# IGresupply2-2.net
KiCad netlist of a schematic drawn in Altium Designer
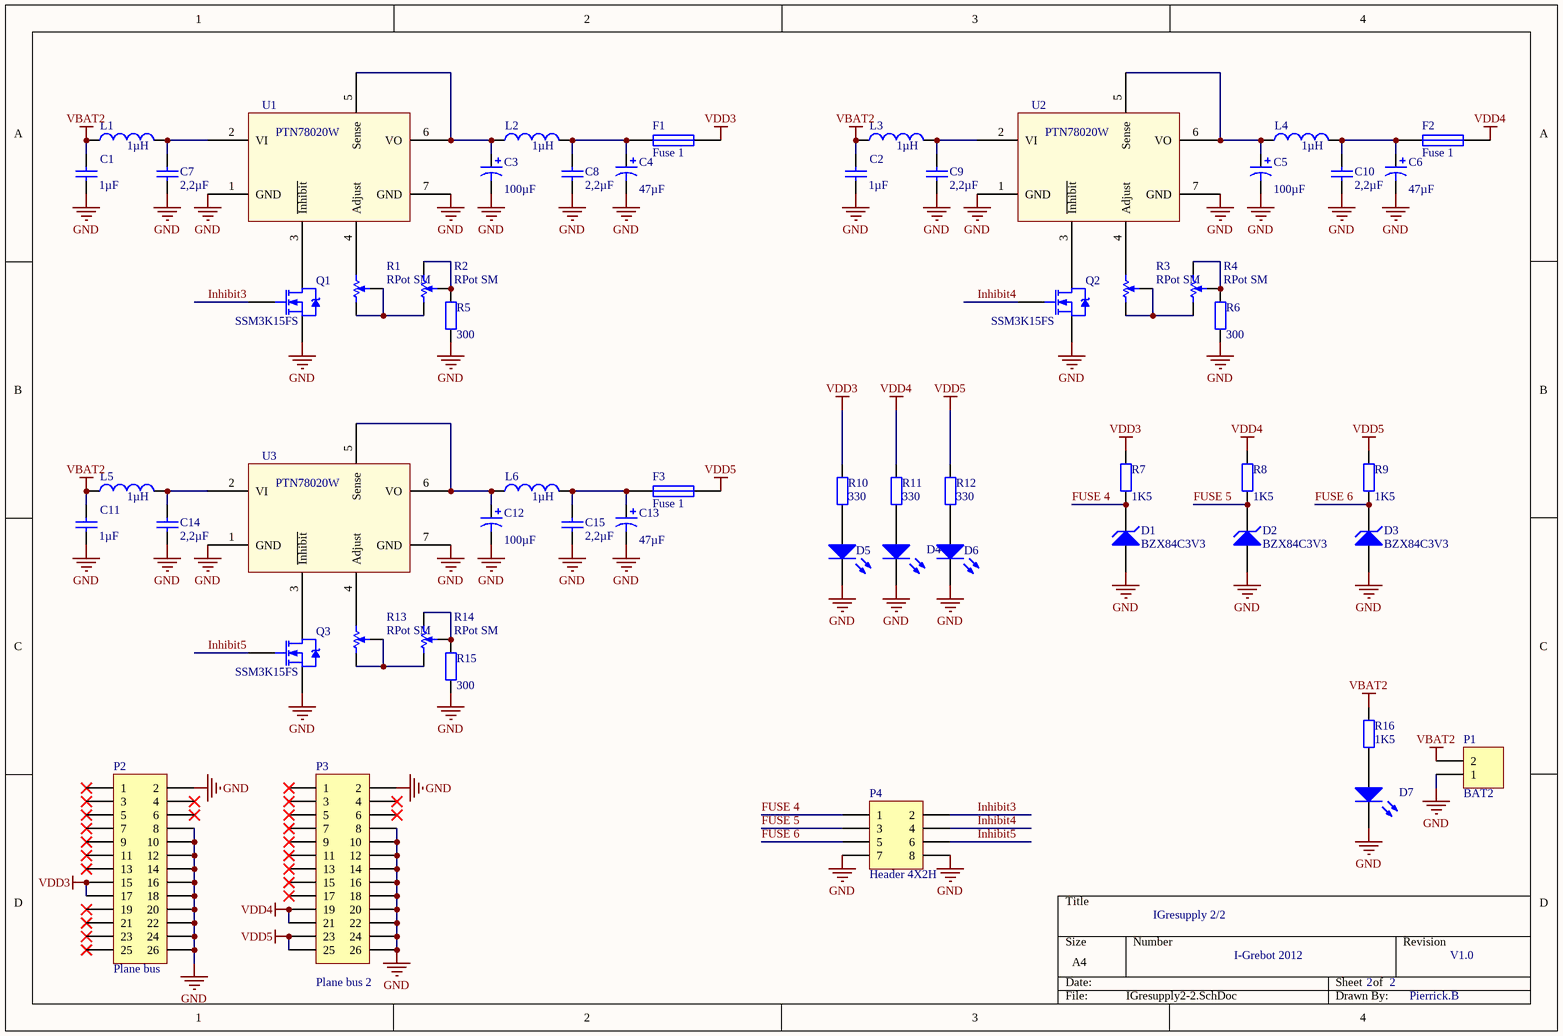
[diagram p0: IGresupply2-2.SchDoc]

(export (version "E")
  (design (tool "Eeschema 10.0.6"))
  (components
    (comp (ref "C1")
      (value "1µF")
      (footprint "Boitier tantale A")
      (description "Capacitor")
      (fields (field (name "Comment") "Cap") (field (name "PUBLISHER") "Altium Limited"))
      (libsource (lib "LIBRARY IGREBOT") (part "Cap"))
    )
    (comp (ref "C2")
      (value "1µF")
      (footprint "Boitier tantale A")
      (description "Capacitor")
      (fields (field (name "Comment") "Cap") (field (name "PUBLISHER") "Altium Limited"))
      (libsource (lib "LIBRARY IGREBOT") (part "Cap"))
    )
    (comp (ref "C3")
      (value "100µF")
      (footprint "Boitier tantale C")
      (description "Polarized Capacitor")
      (fields (field (name "Comment") "Cap Pol") (field (name "PUBLISHER") "Altium Limited"))
      (libsource (lib "LIBRARY IGREBOT") (part "Cap Pol"))
    )
    (comp (ref "C4")
      (value "47µF")
      (footprint "Boitier tantale C")
      (description "Polarized Capacitor")
      (fields (field (name "Comment") "Cap Pol") (field (name "PUBLISHER") "Altium Limited"))
      (libsource (lib "LIBRARY IGREBOT") (part "Cap Pol"))
    )
    (comp (ref "C5")
      (value "100µF")
      (footprint "Boitier tantale C")
      (description "Polarized Capacitor")
      (fields (field (name "Comment") "Cap Pol") (field (name "PUBLISHER") "Altium Limited"))
      (libsource (lib "LIBRARY IGREBOT") (part "Cap Pol"))
    )
    (comp (ref "C6")
      (value "47µF")
      (footprint "Boitier tantale C")
      (description "Polarized Capacitor")
      (fields (field (name "Comment") "Cap Pol") (field (name "PUBLISHER") "Altium Limited"))
      (libsource (lib "LIBRARY IGREBOT") (part "Cap Pol"))
    )
    (comp (ref "C7")
      (value "2,2µF")
      (footprint "Boitier tantale A")
      (description "Capacitor")
      (fields (field (name "Comment") "Cap") (field (name "PUBLISHER") "Altium Limited"))
      (libsource (lib "LIBRARY IGREBOT") (part "Cap"))
    )
    (comp (ref "C8")
      (value "2,2µF")
      (footprint "Boitier tantale A")
      (description "Capacitor")
      (fields (field (name "Comment") "Cap") (field (name "PUBLISHER") "Altium Limited"))
      (libsource (lib "LIBRARY IGREBOT") (part "Cap"))
    )
    (comp (ref "C9")
      (value "2,2µF")
      (footprint "Boitier tantale A")
      (description "Capacitor")
      (fields (field (name "Comment") "Cap") (field (name "PUBLISHER") "Altium Limited"))
      (libsource (lib "LIBRARY IGREBOT") (part "Cap"))
    )
    (comp (ref "C10")
      (value "2,2µF")
      (footprint "Boitier tantale A")
      (description "Capacitor")
      (fields (field (name "Comment") "Cap") (field (name "PUBLISHER") "Altium Limited"))
      (libsource (lib "LIBRARY IGREBOT") (part "Cap"))
    )
    (comp (ref "C11")
      (value "1µF")
      (footprint "Boitier tantale A")
      (description "Capacitor")
      (fields (field (name "Comment") "Cap") (field (name "PUBLISHER") "Altium Limited"))
      (libsource (lib "LIBRARY IGREBOT") (part "Cap"))
    )
    (comp (ref "C12")
      (value "100µF")
      (footprint "Boitier tantale C")
      (description "Polarized Capacitor")
      (fields (field (name "Comment") "Cap Pol") (field (name "PUBLISHER") "Altium Limited"))
      (libsource (lib "LIBRARY IGREBOT") (part "Cap Pol"))
    )
    (comp (ref "C13")
      (value "47µF")
      (footprint "Boitier tantale C")
      (description "Polarized Capacitor")
      (fields (field (name "Comment") "Cap Pol") (field (name "PUBLISHER") "Altium Limited"))
      (libsource (lib "LIBRARY IGREBOT") (part "Cap Pol"))
    )
    (comp (ref "C14")
      (value "2,2µF")
      (footprint "Boitier tantale A")
      (description "Capacitor")
      (fields (field (name "Comment") "Cap") (field (name "PUBLISHER") "Altium Limited"))
      (libsource (lib "LIBRARY IGREBOT") (part "Cap"))
    )
    (comp (ref "C15")
      (value "2,2µF")
      (footprint "Boitier tantale A")
      (description "Capacitor")
      (fields (field (name "Comment") "Cap") (field (name "PUBLISHER") "Altium Limited"))
      (libsource (lib "LIBRARY IGREBOT") (part "Cap"))
    )
    (comp (ref "D1")
      (value "BZX84C3V3")
      (footprint "SOT-23")
      (description "Zener Diode")
      (fields (field (name "PUBLISHER") "Altium Limited"))
      (libsource (lib "LIBRARY IGREBOT") (part "D Zener"))
    )
    (comp (ref "D2")
      (value "BZX84C3V3")
      (footprint "SOT-23")
      (description "Zener Diode")
      (fields (field (name "PUBLISHER") "Altium Limited"))
      (libsource (lib "LIBRARY IGREBOT") (part "D Zener"))
    )
    (comp (ref "D3")
      (value "BZX84C3V3")
      (footprint "SOT-23")
      (description "Zener Diode")
      (fields (field (name "PUBLISHER") "Altium Limited"))
      (libsource (lib "LIBRARY IGREBOT") (part "D Zener"))
    )
    (comp (ref "D4")
      (value "LED1")
      (footprint "HSMS-C110")
      (description "Typical RED GaAs LED")
      (fields (field (name "PUBLISHER") "Altium Limited"))
      (libsource (lib "I-GREBOT 2009") (part "LED1"))
    )
    (comp (ref "D5")
      (value "LED1")
      (footprint "HSMS-C110")
      (description "Typical RED GaAs LED")
      (fields (field (name "PUBLISHER") "Altium Limited"))
      (libsource (lib "I-GREBOT 2009") (part "LED1"))
    )
    (comp (ref "D6")
      (value "LED1")
      (footprint "HSMS-C110")
      (description "Typical RED GaAs LED")
      (fields (field (name "PUBLISHER") "Altium Limited"))
      (libsource (lib "I-GREBOT 2009") (part "LED1"))
    )
    (comp (ref "D7")
      (value "LED1")
      (footprint "HSMS-C110")
      (description "Typical RED GaAs LED")
      (fields (field (name "PUBLISHER") "Altium Limited"))
      (libsource (lib "I-GREBOT 2009") (part "LED1"))
    )
    (comp (ref "F1")
      (value "Fuse 1")
      (footprint "MCCQ-122")
      (description "Fuse")
      (fields (field (name "PUBLISHER") "Altium Limited"))
      (libsource (lib "LIBRARY IGREBOT") (part "Fuse 1"))
    )
    (comp (ref "F2")
      (value "Fuse 1")
      (footprint "MCCQ-122")
      (description "Fuse")
      (fields (field (name "PUBLISHER") "Altium Limited"))
      (libsource (lib "LIBRARY IGREBOT") (part "Fuse 1"))
    )
    (comp (ref "F3")
      (value "Fuse 1")
      (footprint "MCCQ-122")
      (description "Fuse")
      (fields (field (name "PUBLISHER") "Altium Limited"))
      (libsource (lib "LIBRARY IGREBOT") (part "Fuse 1"))
    )
    (comp (ref "L1")
      (value "1µH")
      (footprint "744772010")
      (description "Inductor")
      (fields (field (name "PUBLISHER") "Altium Limited"))
      (libsource (lib "LIBRARY IGREBOT") (part "Inductor"))
    )
    (comp (ref "L2")
      (value "1µH")
      (footprint "744772010")
      (description "Inductor")
      (fields (field (name "PUBLISHER") "Altium Limited"))
      (libsource (lib "LIBRARY IGREBOT") (part "Inductor"))
    )
    (comp (ref "L3")
      (value "1µH")
      (footprint "744772010")
      (description "Inductor")
      (fields (field (name "PUBLISHER") "Altium Limited"))
      (libsource (lib "LIBRARY IGREBOT") (part "Inductor"))
    )
    (comp (ref "L4")
      (value "1µH")
      (footprint "744772010")
      (description "Inductor")
      (fields (field (name "PUBLISHER") "Altium Limited"))
      (libsource (lib "LIBRARY IGREBOT") (part "Inductor"))
    )
    (comp (ref "L5")
      (value "1µH")
      (footprint "744772010")
      (description "Inductor")
      (fields (field (name "PUBLISHER") "Altium Limited"))
      (libsource (lib "LIBRARY IGREBOT") (part "Inductor"))
    )
    (comp (ref "L6")
      (value "1µH")
      (footprint "744772010")
      (description "Inductor")
      (fields (field (name "PUBLISHER") "Altium Limited"))
      (libsource (lib "LIBRARY IGREBOT") (part "Inductor"))
    )
    (comp (ref "P1")
      (value "BAT2")
      (footprint "SL 5.08/90")
      (description "Micro-Fit, 3.0")
      (fields (field (name "PUBLISHER") "Altium Limited"))
      (libsource (lib "I-GREBOT 2010") (part "0436500203"))
    )
    (comp (ref "P2")
      (value "Plane bus")
      (footprint "HDR2X13H")
      (description "Header, 13-Pin, Dual row, Right Angle")
      (fields (field (name "PUBLISHER") "Altium Limited"))
      (libsource (lib "Miscellaneous Connectors") (part "Header 13X2H"))
    )
    (comp (ref "P3")
      (value "Plane bus 2")
      (footprint "HDR2X13H")
      (description "Header, 13-Pin, Dual row, Right Angle")
      (fields (field (name "PUBLISHER") "Altium Limited"))
      (libsource (lib "Miscellaneous Connectors") (part "Header 13X2H"))
    )
    (comp (ref "P4")
      (value "Header 4X2H")
      (footprint "HDR2X4H")
      (description "Header, 4-Pin, Dual row, Right Angle")
      (fields (field (name "PUBLISHER") "Altium Limited"))
      (libsource (lib "Miscellaneous Connectors") (part "Header 4X2H"))
    )
    (comp (ref "Q1")
      (value "SSM3K15FS")
      (footprint "SOT-23")
      (description "N-Channel Power MOSFET")
      (fields (field (name "PUBLISHER") "Altium Limited"))
      (libsource (lib "LIBRARY IGREBOT") (part "NMOS-2"))
    )
    (comp (ref "Q2")
      (value "SSM3K15FS")
      (footprint "SOT-23")
      (description "N-Channel Power MOSFET")
      (fields (field (name "PUBLISHER") "Altium Limited"))
      (libsource (lib "LIBRARY IGREBOT") (part "NMOS-2"))
    )
    (comp (ref "Q3")
      (value "SSM3K15FS")
      (footprint "SOT-23")
      (description "N-Channel Power MOSFET")
      (fields (field (name "PUBLISHER") "Altium Limited"))
      (libsource (lib "LIBRARY IGREBOT") (part "NMOS-2"))
    )
    (comp (ref "R1")
      (value "RPot SM")
      (footprint "3296X")
      (description "Square Trimming Potentiometer")
      (fields (field (name "PUBLISHER") "Altium Limited"))
      (libsource (lib "LIBRARY IGREBOT") (part "RPot SM"))
    )
    (comp (ref "R2")
      (value "RPot SM")
      (footprint "3296X")
      (description "Square Trimming Potentiometer")
      (fields (field (name "PUBLISHER") "Altium Limited"))
      (libsource (lib "LIBRARY IGREBOT") (part "RPot SM"))
    )
    (comp (ref "R3")
      (value "RPot SM")
      (footprint "3296X")
      (description "Square Trimming Potentiometer")
      (fields (field (name "PUBLISHER") "Altium Limited"))
      (libsource (lib "LIBRARY IGREBOT") (part "RPot SM"))
    )
    (comp (ref "R4")
      (value "RPot SM")
      (footprint "3296X")
      (description "Square Trimming Potentiometer")
      (fields (field (name "PUBLISHER") "Altium Limited"))
      (libsource (lib "LIBRARY IGREBOT") (part "RPot SM"))
    )
    (comp (ref "R5")
      (value "300")
      (footprint "0805")
      (description "Resistor")
      (fields (field (name "Comment") "Res2") (field (name "PUBLISHER") "Altium Limited"))
      (libsource (lib "LIBRARY IGREBOT") (part "Res2"))
    )
    (comp (ref "R6")
      (value "300")
      (footprint "0805")
      (description "Resistor")
      (fields (field (name "Comment") "Res2") (field (name "PUBLISHER") "Altium Limited"))
      (libsource (lib "LIBRARY IGREBOT") (part "Res2"))
    )
    (comp (ref "R7")
      (value "1K5")
      (footprint "0805")
      (description "Resistor")
      (fields (field (name "Comment") "Res2") (field (name "PUBLISHER") "Altium Limited"))
      (libsource (lib "LIBRARY IGREBOT") (part "Res2"))
    )
    (comp (ref "R8")
      (value "1K5")
      (footprint "0805")
      (description "Resistor")
      (fields (field (name "Comment") "Res2") (field (name "PUBLISHER") "Altium Limited"))
      (libsource (lib "LIBRARY IGREBOT") (part "Res2"))
    )
    (comp (ref "R9")
      (value "1K5")
      (footprint "0805")
      (description "Resistor")
      (fields (field (name "Comment") "Res2") (field (name "PUBLISHER") "Altium Limited"))
      (libsource (lib "LIBRARY IGREBOT") (part "Res2"))
    )
    (comp (ref "R10")
      (value "330")
      (footprint "0805")
      (description "Resistor")
      (fields (field (name "Comment") "Res2") (field (name "PUBLISHER") "Altium Limited"))
      (libsource (lib "*") (part "Res2"))
    )
    (comp (ref "R11")
      (value "330")
      (footprint "0805")
      (description "Resistor")
      (fields (field (name "Comment") "Res2") (field (name "PUBLISHER") "Altium Limited"))
      (libsource (lib "*") (part "Res2"))
    )
    (comp (ref "R12")
      (value "330")
      (footprint "0805")
      (description "Resistor")
      (fields (field (name "Comment") "Res2") (field (name "PUBLISHER") "Altium Limited"))
      (libsource (lib "*") (part "Res2"))
    )
    (comp (ref "R13")
      (value "RPot SM")
      (footprint "3296X")
      (description "Square Trimming Potentiometer")
      (fields (field (name "PUBLISHER") "Altium Limited"))
      (libsource (lib "LIBRARY IGREBOT") (part "RPot SM"))
    )
    (comp (ref "R14")
      (value "RPot SM")
      (footprint "3296X")
      (description "Square Trimming Potentiometer")
      (fields (field (name "PUBLISHER") "Altium Limited"))
      (libsource (lib "LIBRARY IGREBOT") (part "RPot SM"))
    )
    (comp (ref "R15")
      (value "300")
      (footprint "0805")
      (description "Resistor")
      (fields (field (name "Comment") "Res2") (field (name "PUBLISHER") "Altium Limited"))
      (libsource (lib "LIBRARY IGREBOT") (part "Res2"))
    )
    (comp (ref "R16")
      (value "1K5")
      (footprint "0805")
      (description "Resistor")
      (fields (field (name "Comment") "Res2") (field (name "PUBLISHER") "Altium Limited"))
      (libsource (lib "*") (part "Res2"))
    )
    (comp (ref "U1")
      (value "PTN78020W")
      (footprint "EUK")
      (libsource (lib "LIBRARY IGREBOT") (part "PTN78020W"))
    )
    (comp (ref "U2")
      (value "PTN78020W")
      (footprint "EUK")
      (libsource (lib "LIBRARY IGREBOT") (part "PTN78020W"))
    )
    (comp (ref "U3")
      (value "PTN78020W")
      (footprint "EUK")
      (libsource (lib "LIBRARY IGREBOT") (part "PTN78020W"))
    )
  )
  (nets
    (net (code "1") (name "/FUSE 4") (class "Default")
      (node (ref "D1") (pin "3") (pinfunction "K_3") (pintype "passive"))
      (node (ref "P4") (pin "1") (pinfunction "1_1") (pintype "passive"))
      (node (ref "R7") (pin "1") (pinfunction "1_1") (pintype "passive"))
    )
    (net (code "2") (name "/FUSE 5") (class "Default")
      (node (ref "D2") (pin "3") (pinfunction "K_3") (pintype "passive"))
      (node (ref "P4") (pin "3") (pinfunction "3_3") (pintype "passive"))
      (node (ref "R8") (pin "1") (pinfunction "1_1") (pintype "passive"))
    )
    (net (code "3") (name "/FUSE 6") (class "Default")
      (node (ref "D3") (pin "3") (pinfunction "K_3") (pintype "passive"))
      (node (ref "P4") (pin "5") (pinfunction "5_5") (pintype "passive"))
      (node (ref "R9") (pin "1") (pinfunction "1_1") (pintype "passive"))
    )
    (net (code "4") (name "/Inhibit3") (class "Default")
      (node (ref "P4") (pin "2") (pinfunction "2_2") (pintype "passive"))
      (node (ref "Q1") (pin "1") (pinfunction "G_1") (pintype "passive"))
    )
    (net (code "5") (name "/Inhibit4") (class "Default")
      (node (ref "P4") (pin "4") (pinfunction "4_4") (pintype "passive"))
      (node (ref "Q2") (pin "1") (pinfunction "G_1") (pintype "passive"))
    )
    (net (code "6") (name "/Inhibit5") (class "Default")
      (node (ref "P4") (pin "6") (pinfunction "6_6") (pintype "passive"))
      (node (ref "Q3") (pin "1") (pinfunction "G_1") (pintype "passive"))
    )
    (net (code "7") (name "GND") (class "Default")
      (node (ref "C1") (pin "1") (pinfunction "1_1") (pintype "passive"))
      (node (ref "C10") (pin "1") (pinfunction "1_1") (pintype "passive"))
      (node (ref "C11") (pin "1") (pinfunction "1_1") (pintype "passive"))
      (node (ref "C12") (pin "2") (pinfunction "2_2") (pintype "passive"))
      (node (ref "C13") (pin "2") (pinfunction "2_2") (pintype "passive"))
      (node (ref "C14") (pin "1") (pinfunction "1_1") (pintype "passive"))
      (node (ref "C15") (pin "1") (pinfunction "1_1") (pintype "passive"))
      (node (ref "C2") (pin "1") (pinfunction "1_1") (pintype "passive"))
      (node (ref "C3") (pin "2") (pinfunction "2_2") (pintype "passive"))
      (node (ref "C4") (pin "2") (pinfunction "2_2") (pintype "passive"))
      (node (ref "C5") (pin "2") (pinfunction "2_2") (pintype "passive"))
      (node (ref "C6") (pin "2") (pinfunction "2_2") (pintype "passive"))
      (node (ref "C7") (pin "1") (pinfunction "1_1") (pintype "passive"))
      (node (ref "C8") (pin "1") (pinfunction "1_1") (pintype "passive"))
      (node (ref "C9") (pin "1") (pinfunction "1_1") (pintype "passive"))
      (node (ref "D1") (pin "1") (pinfunction "A_1") (pintype "passive"))
      (node (ref "D2") (pin "1") (pinfunction "A_1") (pintype "passive"))
      (node (ref "D3") (pin "1") (pinfunction "A_1") (pintype "passive"))
      (node (ref "D4") (pin "2") (pinfunction "K_2") (pintype "passive"))
      (node (ref "D5") (pin "2") (pinfunction "K_2") (pintype "passive"))
      (node (ref "D6") (pin "2") (pinfunction "K_2") (pintype "passive"))
      (node (ref "D7") (pin "2") (pinfunction "K_2") (pintype "passive"))
      (node (ref "P1") (pin "1") (pinfunction "1_1") (pintype "passive"))
      (node (ref "P2") (pin "10") (pinfunction "10_10") (pintype "passive"))
      (node (ref "P2") (pin "12") (pinfunction "12_12") (pintype "passive"))
      (node (ref "P2") (pin "14") (pinfunction "14_14") (pintype "passive"))
      (node (ref "P2") (pin "16") (pinfunction "16_16") (pintype "passive"))
      (node (ref "P2") (pin "18") (pinfunction "18_18") (pintype "passive"))
      (node (ref "P2") (pin "2") (pinfunction "2_2") (pintype "passive"))
      (node (ref "P2") (pin "20") (pinfunction "20_20") (pintype "passive"))
      (node (ref "P2") (pin "22") (pinfunction "22_22") (pintype "passive"))
      (node (ref "P2") (pin "24") (pinfunction "24_24") (pintype "passive"))
      (node (ref "P2") (pin "26") (pinfunction "26_26") (pintype "passive"))
      (node (ref "P2") (pin "8") (pinfunction "8_8") (pintype "passive"))
      (node (ref "P3") (pin "10") (pinfunction "10_10") (pintype "passive"))
      (node (ref "P3") (pin "12") (pinfunction "12_12") (pintype "passive"))
      (node (ref "P3") (pin "14") (pinfunction "14_14") (pintype "passive"))
      (node (ref "P3") (pin "16") (pinfunction "16_16") (pintype "passive"))
      (node (ref "P3") (pin "18") (pinfunction "18_18") (pintype "passive"))
      (node (ref "P3") (pin "2") (pinfunction "2_2") (pintype "passive"))
      (node (ref "P3") (pin "20") (pinfunction "20_20") (pintype "passive"))
      (node (ref "P3") (pin "22") (pinfunction "22_22") (pintype "passive"))
      (node (ref "P3") (pin "24") (pinfunction "24_24") (pintype "passive"))
      (node (ref "P3") (pin "26") (pinfunction "26_26") (pintype "passive"))
      (node (ref "P3") (pin "8") (pinfunction "8_8") (pintype "passive"))
      (node (ref "P4") (pin "7") (pinfunction "7_7") (pintype "passive"))
      (node (ref "P4") (pin "8") (pinfunction "8_8") (pintype "passive"))
      (node (ref "Q1") (pin "3") (pinfunction "S_3") (pintype "passive"))
      (node (ref "Q2") (pin "3") (pinfunction "S_3") (pintype "passive"))
      (node (ref "Q3") (pin "3") (pinfunction "S_3") (pintype "passive"))
      (node (ref "R15") (pin "1") (pinfunction "1_1") (pintype "passive"))
      (node (ref "R5") (pin "1") (pinfunction "1_1") (pintype "passive"))
      (node (ref "R6") (pin "1") (pinfunction "1_1") (pintype "passive"))
      (node (ref "U1") (pin "1") (pinfunction "GND_1") (pintype "power_in"))
      (node (ref "U1") (pin "7") (pinfunction "GND_7") (pintype "power_in"))
      (node (ref "U2") (pin "1") (pinfunction "GND_1") (pintype "power_in"))
      (node (ref "U2") (pin "7") (pinfunction "GND_7") (pintype "power_in"))
      (node (ref "U3") (pin "1") (pinfunction "GND_1") (pintype "power_in"))
      (node (ref "U3") (pin "7") (pinfunction "GND_7") (pintype "power_in"))
    )
    (net (code "8") (name "Net-(C4-Pad1)") (class "Default")
      (node (ref "C4") (pin "1") (pinfunction "1_1") (pintype "passive"))
      (node (ref "C8") (pin "2") (pinfunction "2_2") (pintype "passive"))
      (node (ref "F1") (pin "1") (pinfunction "1_1") (pintype "passive"))
      (node (ref "L2") (pin "2") (pinfunction "2_2") (pintype "passive"))
    )
    (net (code "9") (name "Net-(C10-Pad2)") (class "Default")
      (node (ref "C10") (pin "2") (pinfunction "2_2") (pintype "passive"))
      (node (ref "C6") (pin "1") (pinfunction "1_1") (pintype "passive"))
      (node (ref "F2") (pin "1") (pinfunction "1_1") (pintype "passive"))
      (node (ref "L4") (pin "2") (pinfunction "2_2") (pintype "passive"))
    )
    (net (code "10") (name "Net-(C13-Pad1)") (class "Default")
      (node (ref "C13") (pin "1") (pinfunction "1_1") (pintype "passive"))
      (node (ref "C15") (pin "2") (pinfunction "2_2") (pintype "passive"))
      (node (ref "F3") (pin "1") (pinfunction "1_1") (pintype "passive"))
      (node (ref "L6") (pin "2") (pinfunction "2_2") (pintype "passive"))
    )
    (net (code "11") (name "Net-(D4-A)") (class "Default")
      (node (ref "D4") (pin "1") (pinfunction "A_1") (pintype "passive"))
      (node (ref "R11") (pin "1") (pinfunction "1_1") (pintype "passive"))
    )
    (net (code "12") (name "Net-(D5-A)") (class "Default")
      (node (ref "D5") (pin "1") (pinfunction "A_1") (pintype "passive"))
      (node (ref "R10") (pin "1") (pinfunction "1_1") (pintype "passive"))
    )
    (net (code "13") (name "Net-(D6-A)") (class "Default")
      (node (ref "D6") (pin "1") (pinfunction "A_1") (pintype "passive"))
      (node (ref "R12") (pin "1") (pinfunction "1_1") (pintype "passive"))
    )
    (net (code "14") (name "Net-(D7-A)") (class "Default")
      (node (ref "D7") (pin "1") (pinfunction "A_1") (pintype "passive"))
      (node (ref "R16") (pin "1") (pinfunction "1_1") (pintype "passive"))
    )
    (net (code "15") (name "Net-(Q1-D)") (class "Default")
      (node (ref "Q1") (pin "2") (pinfunction "D_2") (pintype "passive"))
      (node (ref "U1") (pin "3") (pinfunction "~{Inhibit}_3") (pintype "power_in"))
    )
    (net (code "16") (name "Net-(Q2-D)") (class "Default")
      (node (ref "Q2") (pin "2") (pinfunction "D_2") (pintype "passive"))
      (node (ref "U2") (pin "3") (pinfunction "~{Inhibit}_3") (pintype "power_in"))
    )
    (net (code "17") (name "Net-(Q3-D)") (class "Default")
      (node (ref "Q3") (pin "2") (pinfunction "D_2") (pintype "passive"))
      (node (ref "U3") (pin "3") (pinfunction "~{Inhibit}_3") (pintype "power_in"))
    )
    (net (code "18") (name "Net-(R1-+)") (class "Default")
      (node (ref "R1") (pin "3") (pinfunction "+_3") (pintype "passive"))
      (node (ref "U1") (pin "4") (pinfunction "Adjust_4") (pintype "power_in"))
    )
    (net (code "19") (name "Net-(R1--)") (class "Default")
      (node (ref "R1") (pin "1") (pinfunction "-_1") (pintype "passive"))
      (node (ref "R1") (pin "2") (pinfunction "W_2") (pintype "passive"))
      (node (ref "R2") (pin "1") (pinfunction "-_1") (pintype "passive"))
    )
    (net (code "20") (name "Net-(R2-+)") (class "Default")
      (node (ref "R2") (pin "2") (pinfunction "W_2") (pintype "passive"))
      (node (ref "R2") (pin "3") (pinfunction "+_3") (pintype "passive"))
      (node (ref "R5") (pin "2") (pinfunction "2_2") (pintype "passive"))
    )
    (net (code "21") (name "Net-(R3-+)") (class "Default")
      (node (ref "R3") (pin "3") (pinfunction "+_3") (pintype "passive"))
      (node (ref "U2") (pin "4") (pinfunction "Adjust_4") (pintype "power_in"))
    )
    (net (code "22") (name "Net-(R3--)") (class "Default")
      (node (ref "R3") (pin "1") (pinfunction "-_1") (pintype "passive"))
      (node (ref "R3") (pin "2") (pinfunction "W_2") (pintype "passive"))
      (node (ref "R4") (pin "1") (pinfunction "-_1") (pintype "passive"))
    )
    (net (code "23") (name "Net-(R4-+)") (class "Default")
      (node (ref "R4") (pin "2") (pinfunction "W_2") (pintype "passive"))
      (node (ref "R4") (pin "3") (pinfunction "+_3") (pintype "passive"))
      (node (ref "R6") (pin "2") (pinfunction "2_2") (pintype "passive"))
    )
    (net (code "24") (name "Net-(R13-+)") (class "Default")
      (node (ref "R13") (pin "3") (pinfunction "+_3") (pintype "passive"))
      (node (ref "U3") (pin "4") (pinfunction "Adjust_4") (pintype "power_in"))
    )
    (net (code "25") (name "Net-(R13--)") (class "Default")
      (node (ref "R13") (pin "1") (pinfunction "-_1") (pintype "passive"))
      (node (ref "R13") (pin "2") (pinfunction "W_2") (pintype "passive"))
      (node (ref "R14") (pin "1") (pinfunction "-_1") (pintype "passive"))
    )
    (net (code "26") (name "Net-(R14-+)") (class "Default")
      (node (ref "R14") (pin "2") (pinfunction "W_2") (pintype "passive"))
      (node (ref "R14") (pin "3") (pinfunction "+_3") (pintype "passive"))
      (node (ref "R15") (pin "2") (pinfunction "2_2") (pintype "passive"))
    )
    (net (code "27") (name "Net-(U1-Sense)") (class "Default")
      (node (ref "C3") (pin "1") (pinfunction "1_1") (pintype "passive"))
      (node (ref "L2") (pin "1") (pinfunction "1_1") (pintype "passive"))
      (node (ref "U1") (pin "5") (pinfunction "Sense_5") (pintype "power_in"))
      (node (ref "U1") (pin "6") (pinfunction "VO_6") (pintype "power_in"))
    )
    (net (code "28") (name "Net-(U1-VI)") (class "Default")
      (node (ref "C7") (pin "2") (pinfunction "2_2") (pintype "passive"))
      (node (ref "L1") (pin "2") (pinfunction "2_2") (pintype "passive"))
      (node (ref "U1") (pin "2") (pinfunction "VI_2") (pintype "power_in"))
    )
    (net (code "29") (name "Net-(U2-Sense)") (class "Default")
      (node (ref "C5") (pin "1") (pinfunction "1_1") (pintype "passive"))
      (node (ref "L4") (pin "1") (pinfunction "1_1") (pintype "passive"))
      (node (ref "U2") (pin "5") (pinfunction "Sense_5") (pintype "power_in"))
      (node (ref "U2") (pin "6") (pinfunction "VO_6") (pintype "power_in"))
    )
    (net (code "30") (name "Net-(U2-VI)") (class "Default")
      (node (ref "C9") (pin "2") (pinfunction "2_2") (pintype "passive"))
      (node (ref "L3") (pin "2") (pinfunction "2_2") (pintype "passive"))
      (node (ref "U2") (pin "2") (pinfunction "VI_2") (pintype "power_in"))
    )
    (net (code "31") (name "Net-(U3-Sense)") (class "Default")
      (node (ref "C12") (pin "1") (pinfunction "1_1") (pintype "passive"))
      (node (ref "L6") (pin "1") (pinfunction "1_1") (pintype "passive"))
      (node (ref "U3") (pin "5") (pinfunction "Sense_5") (pintype "power_in"))
      (node (ref "U3") (pin "6") (pinfunction "VO_6") (pintype "power_in"))
    )
    (net (code "32") (name "Net-(U3-VI)") (class "Default")
      (node (ref "C14") (pin "2") (pinfunction "2_2") (pintype "passive"))
      (node (ref "L5") (pin "2") (pinfunction "2_2") (pintype "passive"))
      (node (ref "U3") (pin "2") (pinfunction "VI_2") (pintype "power_in"))
    )
    (net (code "33") (name "VBAT2") (class "Default")
      (node (ref "C1") (pin "2") (pinfunction "2_2") (pintype "passive"))
      (node (ref "C11") (pin "2") (pinfunction "2_2") (pintype "passive"))
      (node (ref "C2") (pin "2") (pinfunction "2_2") (pintype "passive"))
      (node (ref "L1") (pin "1") (pinfunction "1_1") (pintype "passive"))
      (node (ref "L3") (pin "1") (pinfunction "1_1") (pintype "passive"))
      (node (ref "L5") (pin "1") (pinfunction "1_1") (pintype "passive"))
      (node (ref "P1") (pin "2") (pinfunction "2_2") (pintype "passive"))
      (node (ref "R16") (pin "2") (pinfunction "2_2") (pintype "passive"))
    )
    (net (code "34") (name "VDD3") (class "Default")
      (node (ref "F1") (pin "2") (pinfunction "2_2") (pintype "passive"))
      (node (ref "P2") (pin "15") (pinfunction "15_15") (pintype "passive"))
      (node (ref "P2") (pin "17") (pinfunction "17_17") (pintype "passive"))
      (node (ref "R10") (pin "2") (pinfunction "2_2") (pintype "passive"))
      (node (ref "R7") (pin "2") (pinfunction "2_2") (pintype "passive"))
    )
    (net (code "35") (name "VDD4") (class "Default")
      (node (ref "F2") (pin "2") (pinfunction "2_2") (pintype "passive"))
      (node (ref "P3") (pin "19") (pinfunction "19_19") (pintype "passive"))
      (node (ref "P3") (pin "21") (pinfunction "21_21") (pintype "passive"))
      (node (ref "R11") (pin "2") (pinfunction "2_2") (pintype "passive"))
      (node (ref "R8") (pin "2") (pinfunction "2_2") (pintype "passive"))
    )
    (net (code "36") (name "VDD5") (class "Default")
      (node (ref "F3") (pin "2") (pinfunction "2_2") (pintype "passive"))
      (node (ref "P3") (pin "23") (pinfunction "23_23") (pintype "passive"))
      (node (ref "P3") (pin "25") (pinfunction "25_25") (pintype "passive"))
      (node (ref "R12") (pin "2") (pinfunction "2_2") (pintype "passive"))
      (node (ref "R9") (pin "2") (pinfunction "2_2") (pintype "passive"))
    )
    (net (code "37") (name "unconnected-(P2-Pad1)") (class "Default")
      (node (ref "P2") (pin "1") (pinfunction "1_1") (pintype "passive+no_connect"))
    )
    (net (code "38") (name "unconnected-(P2-Pad3)") (class "Default")
      (node (ref "P2") (pin "3") (pinfunction "3_3") (pintype "passive+no_connect"))
    )
    (net (code "39") (name "unconnected-(P2-Pad4)") (class "Default")
      (node (ref "P2") (pin "4") (pinfunction "4_4") (pintype "passive+no_connect"))
    )
    (net (code "40") (name "unconnected-(P2-Pad5)") (class "Default")
      (node (ref "P2") (pin "5") (pinfunction "5_5") (pintype "passive+no_connect"))
    )
    (net (code "41") (name "unconnected-(P2-Pad6)") (class "Default")
      (node (ref "P2") (pin "6") (pinfunction "6_6") (pintype "passive+no_connect"))
    )
    (net (code "42") (name "unconnected-(P2-Pad7)") (class "Default")
      (node (ref "P2") (pin "7") (pinfunction "7_7") (pintype "passive+no_connect"))
    )
    (net (code "43") (name "unconnected-(P2-Pad9)") (class "Default")
      (node (ref "P2") (pin "9") (pinfunction "9_9") (pintype "passive+no_connect"))
    )
    (net (code "44") (name "unconnected-(P2-Pad11)") (class "Default")
      (node (ref "P2") (pin "11") (pinfunction "11_11") (pintype "passive+no_connect"))
    )
    (net (code "45") (name "unconnected-(P2-Pad13)") (class "Default")
      (node (ref "P2") (pin "13") (pinfunction "13_13") (pintype "passive+no_connect"))
    )
    (net (code "46") (name "unconnected-(P2-Pad19)") (class "Default")
      (node (ref "P2") (pin "19") (pinfunction "19_19") (pintype "passive+no_connect"))
    )
    (net (code "47") (name "unconnected-(P2-Pad21)") (class "Default")
      (node (ref "P2") (pin "21") (pinfunction "21_21") (pintype "passive+no_connect"))
    )
    (net (code "48") (name "unconnected-(P2-Pad23)") (class "Default")
      (node (ref "P2") (pin "23") (pinfunction "23_23") (pintype "passive+no_connect"))
    )
    (net (code "49") (name "unconnected-(P2-Pad25)") (class "Default")
      (node (ref "P2") (pin "25") (pinfunction "25_25") (pintype "passive+no_connect"))
    )
    (net (code "50") (name "unconnected-(P3-Pad1)") (class "Default")
      (node (ref "P3") (pin "1") (pinfunction "1_1") (pintype "passive+no_connect"))
    )
    (net (code "51") (name "unconnected-(P3-Pad3)") (class "Default")
      (node (ref "P3") (pin "3") (pinfunction "3_3") (pintype "passive+no_connect"))
    )
    (net (code "52") (name "unconnected-(P3-Pad4)") (class "Default")
      (node (ref "P3") (pin "4") (pinfunction "4_4") (pintype "passive+no_connect"))
    )
    (net (code "53") (name "unconnected-(P3-Pad5)") (class "Default")
      (node (ref "P3") (pin "5") (pinfunction "5_5") (pintype "passive+no_connect"))
    )
    (net (code "54") (name "unconnected-(P3-Pad6)") (class "Default")
      (node (ref "P3") (pin "6") (pinfunction "6_6") (pintype "passive+no_connect"))
    )
    (net (code "55") (name "unconnected-(P3-Pad7)") (class "Default")
      (node (ref "P3") (pin "7") (pinfunction "7_7") (pintype "passive+no_connect"))
    )
    (net (code "56") (name "unconnected-(P3-Pad9)") (class "Default")
      (node (ref "P3") (pin "9") (pinfunction "9_9") (pintype "passive+no_connect"))
    )
    (net (code "57") (name "unconnected-(P3-Pad11)") (class "Default")
      (node (ref "P3") (pin "11") (pinfunction "11_11") (pintype "passive+no_connect"))
    )
    (net (code "58") (name "unconnected-(P3-Pad13)") (class "Default")
      (node (ref "P3") (pin "13") (pinfunction "13_13") (pintype "passive+no_connect"))
    )
    (net (code "59") (name "unconnected-(P3-Pad15)") (class "Default")
      (node (ref "P3") (pin "15") (pinfunction "15_15") (pintype "passive+no_connect"))
    )
    (net (code "60") (name "unconnected-(P3-Pad17)") (class "Default")
      (node (ref "P3") (pin "17") (pinfunction "17_17") (pintype "passive+no_connect"))
    )
  )
)
